# sensorbug_v1.net
KiCad netlist of a schematic drawn in EAGLE
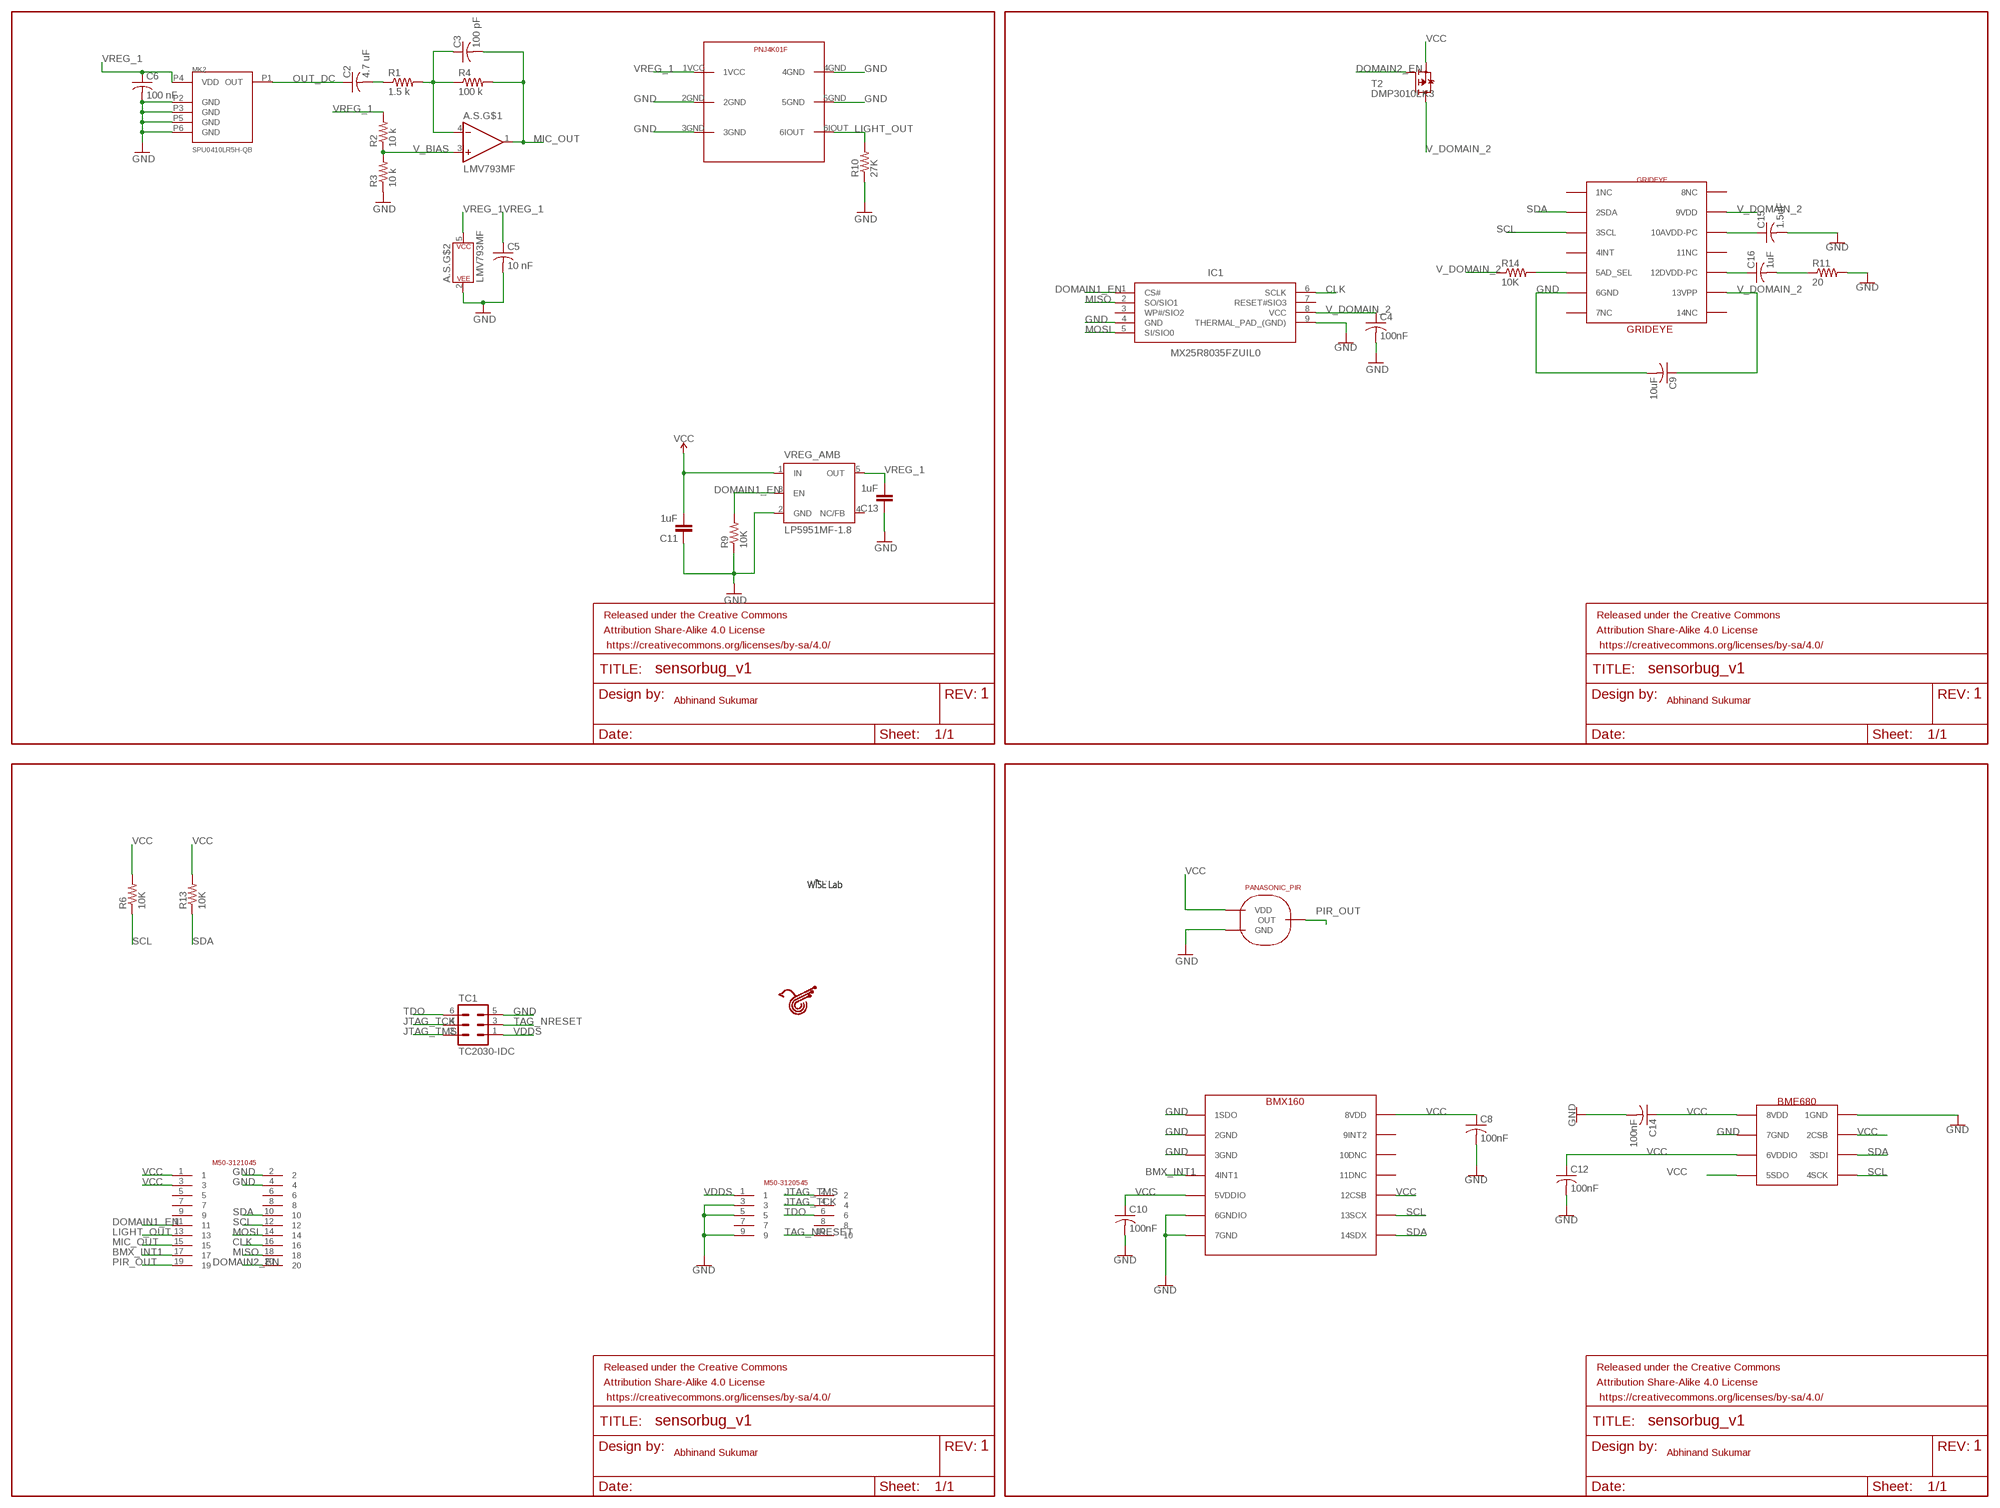
[diagram p0: schematic, sheet 1]

(export (version "E")
  (design (tool "Eeschema 10.0.6"))
  (components
    (comp (ref "A.S.")
      (value "LMV793MF")
      (footprint "eagle-import:SOT23-5")
      (libsource (lib "eagle-import") (part "LMV793MF"))
    )
    (comp (ref "BME")
      (value "BME680")
      (footprint "eagle-import:BME680_LGA")
      (libsource (lib "eagle-import") (part "BME680"))
    )
    (comp (ref "BMX")
      (value "BMX160")
      (footprint "eagle-import:LGA")
      (libsource (lib "eagle-import") (part "BMX160"))
    )
    (comp (ref "C2")
      (value "4.7 uF")
      (footprint "eagle-import:C0603")
      (libsource (lib "eagle-import") (part "C-USC0603"))
    )
    (comp (ref "C3")
      (value "100 pF")
      (footprint "eagle-import:C0603")
      (libsource (lib "eagle-import") (part "C-USC0603"))
    )
    (comp (ref "C4")
      (value "100nF")
      (footprint "eagle-import:C0603")
      (libsource (lib "eagle-import") (part "C-USC0603"))
    )
    (comp (ref "C5")
      (value "10 nF")
      (footprint "eagle-import:C0603")
      (libsource (lib "eagle-import") (part "C-USC0603"))
    )
    (comp (ref "C6")
      (value "100 nF")
      (footprint "eagle-import:C0603")
      (libsource (lib "eagle-import") (part "C-USC0603"))
    )
    (comp (ref "C8")
      (value "100nF")
      (footprint "eagle-import:C0603")
      (libsource (lib "eagle-import") (part "C-USC0603"))
    )
    (comp (ref "C9")
      (value "10uF")
      (footprint "eagle-import:C0603")
      (libsource (lib "eagle-import") (part "C-USC0603"))
    )
    (comp (ref "C10")
      (value "100nF")
      (footprint "eagle-import:C0603")
      (libsource (lib "eagle-import") (part "C-USC0603"))
    )
    (comp (ref "C11")
      (value "1uF")
      (footprint "eagle-import:C0603")
      (libsource (lib "eagle-import") (part "C-EUC0603"))
    )
    (comp (ref "C12")
      (value "100nF")
      (footprint "eagle-import:C0603")
      (libsource (lib "eagle-import") (part "C-USC0603"))
    )
    (comp (ref "C13")
      (value "1uF")
      (footprint "eagle-import:C0603")
      (libsource (lib "eagle-import") (part "C-EUC0603"))
    )
    (comp (ref "C14")
      (value "100nF")
      (footprint "eagle-import:C0603")
      (libsource (lib "eagle-import") (part "C-USC0603"))
    )
    (comp (ref "C15")
      (value "1.5uF")
      (footprint "eagle-import:C0603")
      (libsource (lib "eagle-import") (part "C-USC0603"))
    )
    (comp (ref "C16")
      (value "1uF")
      (footprint "eagle-import:C0603")
      (libsource (lib "eagle-import") (part "C-USC0603"))
    )
    (comp (ref "FRAME1")
      (value "FRAME-LETTER")
      (footprint "eagle-import:CREATIVE_COMMONS")
      (libsource (lib "eagle-import") (part "FRAME-LETTER"))
    )
    (comp (ref "FRAME2")
      (value "FRAME-LETTER")
      (footprint "eagle-import:CREATIVE_COMMONS")
      (libsource (lib "eagle-import") (part "FRAME-LETTER"))
    )
    (comp (ref "FRAME3")
      (value "FRAME-LETTER")
      (footprint "eagle-import:CREATIVE_COMMONS")
      (libsource (lib "eagle-import") (part "FRAME-LETTER"))
    )
    (comp (ref "FRAME4")
      (value "FRAME-LETTER")
      (footprint "eagle-import:CREATIVE_COMMONS")
      (libsource (lib "eagle-import") (part "FRAME-LETTER"))
    )
    (comp (ref "GRIDEYE")
      (value "GRIDEYE")
      (footprint "eagle-import:GRIDEYE")
      (libsource (lib "eagle-import") (part "GRIDEYE"))
    )
    (comp (ref "IC1")
      (value "MX25R8035FZUIL0")
      (footprint "eagle-import:USON-8L")
      (libsource (lib "eagle-import") (part "MX25R8035FZUIL0"))
    )
    (comp (ref "LIGHT")
      (value "PNJ4K01F")
      (footprint "eagle-import:PNJ4K01F")
      (libsource (lib "eagle-import") (part "PNJ4K01F"))
    )
    (comp (ref "MK2")
      (value "SPU0410LR5H-QB")
      (footprint "eagle-import:SPU0410LR5H-QB")
      (libsource (lib "eagle-import") (part "SPU0410LR5H-QB"))
    )
    (comp (ref "R1")
      (value "1.5 k")
      (footprint "eagle-import:R0603")
      (libsource (lib "eagle-import") (part "R-US_R0603"))
    )
    (comp (ref "R2")
      (value "10 k")
      (footprint "eagle-import:R0603")
      (libsource (lib "eagle-import") (part "R-US_R0603"))
    )
    (comp (ref "R3")
      (value "10 k")
      (footprint "eagle-import:R0603")
      (libsource (lib "eagle-import") (part "R-US_R0603"))
    )
    (comp (ref "R4")
      (value "100 k")
      (footprint "eagle-import:R0603")
      (libsource (lib "eagle-import") (part "R-US_R0603"))
    )
    (comp (ref "R6")
      (value "10K")
      (footprint "eagle-import:R0603")
      (libsource (lib "eagle-import") (part "R-US_R0603"))
    )
    (comp (ref "R9")
      (value "10K")
      (footprint "eagle-import:R0603")
      (libsource (lib "eagle-import") (part "R-US_R0603"))
    )
    (comp (ref "R10")
      (value "27K")
      (footprint "eagle-import:R0603")
      (libsource (lib "eagle-import") (part "R-US_R0603"))
    )
    (comp (ref "R11")
      (value "20")
      (footprint "eagle-import:R0603")
      (libsource (lib "eagle-import") (part "R-US_R0603"))
    )
    (comp (ref "R13")
      (value "10K")
      (footprint "eagle-import:R0603")
      (libsource (lib "eagle-import") (part "R-US_R0603"))
    )
    (comp (ref "R14")
      (value "10K")
      (footprint "eagle-import:R0603")
      (libsource (lib "eagle-import") (part "R-US_R0603"))
    )
    (comp (ref "T2")
      (value "DMP3010LK3")
      (footprint "eagle-import:TO252")
      (libsource (lib "eagle-import") (part "SPD30P06PTO252"))
    )
    (comp (ref "TC1")
      (value "TC2030-IDC")
      (footprint "eagle-import:TC2030-IDC")
      (libsource (lib "eagle-import") (part "TC2030-IDC"))
    )
    (comp (ref "U$2")
      (value "WISELAB_LOGO-M")
      (footprint "eagle-import:WISELAB_LOGO_M")
      (libsource (lib "eagle-import") (part "WISELAB_LOGO-M"))
    )
    (comp (ref "U$3")
      (value "EKMB1201112")
      (footprint "eagle-import:EKMB1201112")
      (libsource (lib "eagle-import") (part "EKMB1201112"))
    )
    (comp (ref "U$4")
      (value "M50-3121045")
      (footprint "eagle-import:M50-3121045")
      (libsource (lib "eagle-import") (part "M50-3121045"))
    )
    (comp (ref "U$5")
      (value "M50-3120545")
      (footprint "eagle-import:M50-3100545")
      (libsource (lib "eagle-import") (part "M50-3120545"))
    )
    (comp (ref "U$6")
      (value "OPENCHIR_LOGO_PCB-M")
      (footprint "eagle-import:OPENCHIRP_LOGO_M")
      (libsource (lib "eagle-import") (part "OPENCHIR_LOGO_PCB-M"))
    )
    (comp (ref "VREG_AMB")
      (value "LP5951MF-1.8")
      (footprint "eagle-import:SOT23-DBV")
      (libsource (lib "eagle-import") (part "LP5951MF-1.8"))
    )
  )
  (nets
    (net (code "1") (name "/BMX_INT1") (class "Default")
      (node (ref "BMX") (pin "4INT1") (pinfunction "4INT1_4INT1") (pintype "bidirectional"))
      (node (ref "U$4") (pin "17") (pinfunction "17_17") (pintype "bidirectional"))
    )
    (net (code "2") (name "/CLK") (class "Default")
      (node (ref "IC1") (pin "6") (pinfunction "SCLK_6") (pintype "input"))
      (node (ref "U$4") (pin "16") (pinfunction "16_16") (pintype "bidirectional"))
    )
    (net (code "3") (name "/DOMAIN1_EN") (class "Default")
      (node (ref "IC1") (pin "1") (pinfunction "CS#_1") (pintype "input"))
      (node (ref "R9") (pin "2") (pinfunction "2_2") (pintype "passive"))
      (node (ref "U$4") (pin "11") (pinfunction "11_11") (pintype "bidirectional"))
      (node (ref "VREG_AMB") (pin "3") (pinfunction "EN_3") (pintype "input"))
    )
    (net (code "4") (name "/DOMAIN2_EN") (class "Default")
      (node (ref "T2") (pin "1") (pinfunction "G_1") (pintype "passive"))
      (node (ref "U$4") (pin "20") (pinfunction "20_20") (pintype "bidirectional"))
    )
    (net (code "5") (name "/JTAG_TCK") (class "Default")
      (node (ref "TC1") (pin "4") (pinfunction "4_4") (pintype "passive"))
      (node (ref "U$5") (pin "4") (pinfunction "4_4") (pintype "bidirectional"))
    )
    (net (code "6") (name "/JTAG_TMS") (class "Default")
      (node (ref "TC1") (pin "2") (pinfunction "2_2") (pintype "passive"))
      (node (ref "U$5") (pin "2") (pinfunction "2_2") (pintype "bidirectional"))
    )
    (net (code "7") (name "/LIGHT_OUT") (class "Default")
      (node (ref "LIGHT") (pin "6IOUT") (pinfunction "6IOUT_6IOUT") (pintype "bidirectional"))
      (node (ref "R10") (pin "2") (pinfunction "2_2") (pintype "passive"))
      (node (ref "U$4") (pin "13") (pinfunction "13_13") (pintype "bidirectional"))
    )
    (net (code "8") (name "/MIC_OUT") (class "Default")
      (node (ref "A.S.") (pin "1") (pinfunction "OUT_1") (pintype "output"))
      (node (ref "C3") (pin "2") (pinfunction "2_2") (pintype "passive"))
      (node (ref "R4") (pin "2") (pinfunction "2_2") (pintype "passive"))
      (node (ref "U$4") (pin "15") (pinfunction "15_15") (pintype "bidirectional"))
    )
    (net (code "9") (name "/MISO") (class "Default")
      (node (ref "IC1") (pin "2") (pinfunction "SO/SIO1_2") (pintype "input"))
      (node (ref "U$4") (pin "18") (pinfunction "18_18") (pintype "bidirectional"))
    )
    (net (code "10") (name "/MOSI") (class "Default")
      (node (ref "IC1") (pin "5") (pinfunction "SI/SIO0_5") (pintype "input"))
      (node (ref "U$4") (pin "14") (pinfunction "14_14") (pintype "bidirectional"))
    )
    (net (code "11") (name "/OUT_DC") (class "Default")
      (node (ref "C2") (pin "1") (pinfunction "1_1") (pintype "passive"))
      (node (ref "MK2") (pin "P1") (pinfunction "OUT_P1") (pintype "output"))
    )
    (net (code "12") (name "/PIR_OUT") (class "Default")
      (node (ref "U$3") (pin "OUT") (pinfunction "OUT_OUT") (pintype "bidirectional"))
      (node (ref "U$4") (pin "19") (pinfunction "19_19") (pintype "bidirectional"))
    )
    (net (code "13") (name "/SCL") (class "Default")
      (node (ref "BME") (pin "4SCK") (pinfunction "4SCK_4SCK") (pintype "bidirectional"))
      (node (ref "BMX") (pin "13SCX") (pinfunction "13SCX_13SCX") (pintype "bidirectional"))
      (node (ref "GRIDEYE") (pin "3") (pinfunction "3SCL_3") (pintype "bidirectional"))
      (node (ref "R6") (pin "1") (pinfunction "1_1") (pintype "passive"))
      (node (ref "U$4") (pin "12") (pinfunction "12_12") (pintype "bidirectional"))
    )
    (net (code "14") (name "/SDA") (class "Default")
      (node (ref "BME") (pin "3SDI") (pinfunction "3SDI_3SDI") (pintype "bidirectional"))
      (node (ref "BMX") (pin "14SDX") (pinfunction "14SDX_14SDX") (pintype "bidirectional"))
      (node (ref "GRIDEYE") (pin "2") (pinfunction "2SDA_2") (pintype "bidirectional"))
      (node (ref "R13") (pin "1") (pinfunction "1_1") (pintype "passive"))
      (node (ref "U$4") (pin "10") (pinfunction "10_10") (pintype "bidirectional"))
    )
    (net (code "15") (name "/TAG_NRESET") (class "Default")
      (node (ref "TC1") (pin "3") (pinfunction "3_3") (pintype "passive"))
      (node (ref "U$5") (pin "10") (pinfunction "10_10") (pintype "bidirectional"))
    )
    (net (code "16") (name "/TDO") (class "Default")
      (node (ref "TC1") (pin "6") (pinfunction "6_6") (pintype "passive"))
      (node (ref "U$5") (pin "6") (pinfunction "6_6") (pintype "bidirectional"))
    )
    (net (code "17") (name "/VDDS") (class "Default")
      (node (ref "TC1") (pin "1") (pinfunction "1_1") (pintype "passive"))
      (node (ref "U$5") (pin "1") (pinfunction "1_1") (pintype "bidirectional"))
    )
    (net (code "18") (name "/VREG_1") (class "Default")
      (node (ref "A.S.") (pin "5") (pinfunction "P$V+_5") (pintype "bidirectional"))
      (node (ref "C13") (pin "2") (pinfunction "2_2") (pintype "passive"))
      (node (ref "C5") (pin "1") (pinfunction "1_1") (pintype "passive"))
      (node (ref "C6") (pin "1") (pinfunction "1_1") (pintype "passive"))
      (node (ref "LIGHT") (pin "1VCC") (pinfunction "1VCC_1VCC") (pintype "bidirectional"))
      (node (ref "MK2") (pin "P4") (pinfunction "VDD_P4") (pintype "power_in"))
      (node (ref "R2") (pin "2") (pinfunction "2_2") (pintype "passive"))
      (node (ref "VREG_AMB") (pin "5") (pinfunction "OUT_5") (pintype "output"))
    )
    (net (code "19") (name "/V_BIAS") (class "Default")
      (node (ref "A.S.") (pin "3") (pinfunction "+IN_3") (pintype "input"))
      (node (ref "R2") (pin "1") (pinfunction "1_1") (pintype "passive"))
      (node (ref "R3") (pin "2") (pinfunction "2_2") (pintype "passive"))
    )
    (net (code "20") (name "/V_DOMAIN_2") (class "Default")
      (node (ref "C4") (pin "1") (pinfunction "1_1") (pintype "passive"))
      (node (ref "C9") (pin "1") (pinfunction "1_1") (pintype "passive"))
      (node (ref "GRIDEYE") (pin "13") (pinfunction "13VPP_13") (pintype "bidirectional"))
      (node (ref "GRIDEYE") (pin "9") (pinfunction "9VDD_9") (pintype "bidirectional"))
      (node (ref "IC1") (pin "8") (pinfunction "VCC_8") (pintype "input"))
      (node (ref "R14") (pin "1") (pinfunction "1_1") (pintype "passive"))
      (node (ref "T2") (pin "3") (pinfunction "D_3") (pintype "passive"))
    )
    (net (code "21") (name "GND") (class "Default")
      (node (ref "A.S.") (pin "2") (pinfunction "P$V-_2") (pintype "bidirectional"))
      (node (ref "BME") (pin "1GND") (pinfunction "1GND_1GND") (pintype "bidirectional"))
      (node (ref "BME") (pin "7GND") (pinfunction "7GND_7GND") (pintype "bidirectional"))
      (node (ref "BMX") (pin "1SDO") (pinfunction "1SDO_1SDO") (pintype "bidirectional"))
      (node (ref "BMX") (pin "2GND") (pinfunction "2GND_2GND") (pintype "bidirectional"))
      (node (ref "BMX") (pin "3GND") (pinfunction "3GND_3GND") (pintype "bidirectional"))
      (node (ref "BMX") (pin "6GNDIO") (pinfunction "6GNDIO_6GNDIO") (pintype "bidirectional"))
      (node (ref "BMX") (pin "7GND") (pinfunction "7GND_7GND") (pintype "bidirectional"))
      (node (ref "C10") (pin "2") (pinfunction "2_2") (pintype "passive"))
      (node (ref "C11") (pin "1") (pinfunction "1_1") (pintype "passive"))
      (node (ref "C12") (pin "2") (pinfunction "2_2") (pintype "passive"))
      (node (ref "C13") (pin "1") (pinfunction "1_1") (pintype "passive"))
      (node (ref "C14") (pin "2") (pinfunction "2_2") (pintype "passive"))
      (node (ref "C15") (pin "2") (pinfunction "2_2") (pintype "passive"))
      (node (ref "C4") (pin "2") (pinfunction "2_2") (pintype "passive"))
      (node (ref "C5") (pin "2") (pinfunction "2_2") (pintype "passive"))
      (node (ref "C6") (pin "2") (pinfunction "2_2") (pintype "passive"))
      (node (ref "C8") (pin "2") (pinfunction "2_2") (pintype "passive"))
      (node (ref "C9") (pin "2") (pinfunction "2_2") (pintype "passive"))
      (node (ref "GRIDEYE") (pin "6") (pinfunction "6GND_6") (pintype "bidirectional"))
      (node (ref "IC1") (pin "4") (pinfunction "GND_4") (pintype "input"))
      (node (ref "IC1") (pin "9") (pinfunction "THERMAL_PAD_(GND)_9") (pintype "input"))
      (node (ref "LIGHT") (pin "2GND") (pinfunction "2GND_2GND") (pintype "bidirectional"))
      (node (ref "LIGHT") (pin "3GND") (pinfunction "3GND_3GND") (pintype "bidirectional"))
      (node (ref "LIGHT") (pin "4GND") (pinfunction "4GND_4GND") (pintype "bidirectional"))
      (node (ref "LIGHT") (pin "5GND") (pinfunction "5GND_5GND") (pintype "bidirectional"))
      (node (ref "MK2") (pin "P2") (pinfunction "GND_P2") (pintype "power_in"))
      (node (ref "MK2") (pin "P3") (pinfunction "GND_P3") (pintype "power_in"))
      (node (ref "MK2") (pin "P5") (pinfunction "GND_P5") (pintype "power_in"))
      (node (ref "MK2") (pin "P6") (pinfunction "GND_P6") (pintype "power_in"))
      (node (ref "R10") (pin "1") (pinfunction "1_1") (pintype "passive"))
      (node (ref "R11") (pin "2") (pinfunction "2_2") (pintype "passive"))
      (node (ref "R3") (pin "1") (pinfunction "1_1") (pintype "passive"))
      (node (ref "R9") (pin "1") (pinfunction "1_1") (pintype "passive"))
      (node (ref "TC1") (pin "5") (pinfunction "5_5") (pintype "passive"))
      (node (ref "U$3") (pin "GND") (pinfunction "GND_GND") (pintype "bidirectional"))
      (node (ref "U$4") (pin "2") (pinfunction "2_2") (pintype "bidirectional"))
      (node (ref "U$4") (pin "4") (pinfunction "4_4") (pintype "bidirectional"))
      (node (ref "U$5") (pin "3") (pinfunction "3_3") (pintype "bidirectional"))
      (node (ref "U$5") (pin "5") (pinfunction "5_5") (pintype "bidirectional"))
      (node (ref "U$5") (pin "9") (pinfunction "9_9") (pintype "bidirectional"))
      (node (ref "VREG_AMB") (pin "2") (pinfunction "GND_2") (pintype "power_in"))
    )
    (net (code "22") (name "Net-(A.S.A--IN)") (class "Default")
      (node (ref "A.S.") (pin "4") (pinfunction "-IN_4") (pintype "input"))
      (node (ref "C3") (pin "1") (pinfunction "1_1") (pintype "passive"))
      (node (ref "R1") (pin "2") (pinfunction "2_2") (pintype "passive"))
      (node (ref "R4") (pin "1") (pinfunction "1_1") (pintype "passive"))
    )
    (net (code "23") (name "Net-(C2-Pad2)") (class "Default")
      (node (ref "C2") (pin "2") (pinfunction "2_2") (pintype "passive"))
      (node (ref "R1") (pin "1") (pinfunction "1_1") (pintype "passive"))
    )
    (net (code "24") (name "Net-(C16-Pad2)") (class "Default")
      (node (ref "C16") (pin "2") (pinfunction "2_2") (pintype "passive"))
      (node (ref "R11") (pin "1") (pinfunction "1_1") (pintype "passive"))
    )
    (net (code "25") (name "Net-(GRIDEYE-5AD_SEL)") (class "Default")
      (node (ref "GRIDEYE") (pin "5") (pinfunction "5AD_SEL_5") (pintype "bidirectional"))
      (node (ref "R14") (pin "2") (pinfunction "2_2") (pintype "passive"))
    )
    (net (code "26") (name "Net-(GRIDEYE-10AVDD-PC)") (class "Default")
      (node (ref "C15") (pin "1") (pinfunction "1_1") (pintype "passive"))
      (node (ref "GRIDEYE") (pin "10") (pinfunction "10AVDD-PC_10") (pintype "bidirectional"))
    )
    (net (code "27") (name "Net-(GRIDEYE-12DVDD-PC)") (class "Default")
      (node (ref "C16") (pin "1") (pinfunction "1_1") (pintype "passive"))
      (node (ref "GRIDEYE") (pin "12") (pinfunction "12DVDD-PC_12") (pintype "bidirectional"))
    )
    (net (code "28") (name "VCC") (class "Default")
      (node (ref "BME") (pin "2CSB") (pinfunction "2CSB_2CSB") (pintype "bidirectional"))
      (node (ref "BME") (pin "5SDO") (pinfunction "5SDO_5SDO") (pintype "bidirectional"))
      (node (ref "BME") (pin "6VDDIO") (pinfunction "6VDDIO_6VDDIO") (pintype "bidirectional"))
      (node (ref "BME") (pin "8VDD") (pinfunction "8VDD_8VDD") (pintype "bidirectional"))
      (node (ref "BMX") (pin "12CSB") (pinfunction "12CSB_12CSB") (pintype "bidirectional"))
      (node (ref "BMX") (pin "5VDDIO") (pinfunction "5VDDIO_5VDDIO") (pintype "bidirectional"))
      (node (ref "BMX") (pin "8VDD") (pinfunction "8VDD_8VDD") (pintype "bidirectional"))
      (node (ref "C10") (pin "1") (pinfunction "1_1") (pintype "passive"))
      (node (ref "C11") (pin "2") (pinfunction "2_2") (pintype "passive"))
      (node (ref "C12") (pin "1") (pinfunction "1_1") (pintype "passive"))
      (node (ref "C14") (pin "1") (pinfunction "1_1") (pintype "passive"))
      (node (ref "C8") (pin "1") (pinfunction "1_1") (pintype "passive"))
      (node (ref "R13") (pin "2") (pinfunction "2_2") (pintype "passive"))
      (node (ref "R6") (pin "2") (pinfunction "2_2") (pintype "passive"))
      (node (ref "T2") (pin "2") (pinfunction "S_2") (pintype "passive"))
      (node (ref "U$3") (pin "VDD") (pinfunction "VDD_VDD") (pintype "bidirectional"))
      (node (ref "U$4") (pin "1") (pinfunction "1_1") (pintype "bidirectional"))
      (node (ref "U$4") (pin "3") (pinfunction "3_3") (pintype "bidirectional"))
      (node (ref "VREG_AMB") (pin "1") (pinfunction "IN_1") (pintype "input"))
    )
    (net (code "29") (name "unconnected-(BMX-Pad9INT2)") (class "Default")
      (node (ref "BMX") (pin "9INT2") (pinfunction "9INT2_9INT2") (pintype "bidirectional"))
    )
    (net (code "30") (name "unconnected-(BMX-Pad10DNC)") (class "Default")
      (node (ref "BMX") (pin "10DNC") (pinfunction "10DNC_10DNC") (pintype "bidirectional"))
    )
    (net (code "31") (name "unconnected-(BMX-Pad11DNC)") (class "Default")
      (node (ref "BMX") (pin "11DNC") (pinfunction "11DNC_11DNC") (pintype "bidirectional"))
    )
    (net (code "32") (name "unconnected-(GRIDEYE-1NC-Pad1)") (class "Default")
      (node (ref "GRIDEYE") (pin "1") (pinfunction "1NC_1") (pintype "bidirectional"))
    )
    (net (code "33") (name "unconnected-(GRIDEYE-4INT-Pad4)") (class "Default")
      (node (ref "GRIDEYE") (pin "4") (pinfunction "4INT_4") (pintype "bidirectional"))
    )
    (net (code "34") (name "unconnected-(GRIDEYE-7NC-Pad7)") (class "Default")
      (node (ref "GRIDEYE") (pin "7") (pinfunction "7NC_7") (pintype "bidirectional"))
    )
    (net (code "35") (name "unconnected-(GRIDEYE-8NC-Pad8)") (class "Default")
      (node (ref "GRIDEYE") (pin "8") (pinfunction "8NC_8") (pintype "bidirectional"))
    )
    (net (code "36") (name "unconnected-(GRIDEYE-11NC-Pad11)") (class "Default")
      (node (ref "GRIDEYE") (pin "11") (pinfunction "11NC_11") (pintype "bidirectional"))
    )
    (net (code "37") (name "unconnected-(GRIDEYE-14NC-Pad14)") (class "Default")
      (node (ref "GRIDEYE") (pin "14") (pinfunction "14NC_14") (pintype "bidirectional"))
    )
    (net (code "38") (name "unconnected-(IC1-RESET#SIO3-Pad7)") (class "Default")
      (node (ref "IC1") (pin "7") (pinfunction "RESET#SIO3_7") (pintype "input"))
    )
    (net (code "39") (name "unconnected-(IC1-WP#{slash}SIO2-Pad3)") (class "Default")
      (node (ref "IC1") (pin "3") (pinfunction "WP#/SIO2_3") (pintype "input"))
    )
    (net (code "40") (name "unconnected-(U$4-Pad5)") (class "Default")
      (node (ref "U$4") (pin "5") (pinfunction "5_5") (pintype "bidirectional"))
    )
    (net (code "41") (name "unconnected-(U$4-Pad6)") (class "Default")
      (node (ref "U$4") (pin "6") (pinfunction "6_6") (pintype "bidirectional"))
    )
    (net (code "42") (name "unconnected-(U$4-Pad7)") (class "Default")
      (node (ref "U$4") (pin "7") (pinfunction "7_7") (pintype "bidirectional"))
    )
    (net (code "43") (name "unconnected-(U$4-Pad8)") (class "Default")
      (node (ref "U$4") (pin "8") (pinfunction "8_8") (pintype "bidirectional"))
    )
    (net (code "44") (name "unconnected-(U$4-Pad9)") (class "Default")
      (node (ref "U$4") (pin "9") (pinfunction "9_9") (pintype "bidirectional"))
    )
    (net (code "45") (name "unconnected-(U$5-Pad7)") (class "Default")
      (node (ref "U$5") (pin "7") (pinfunction "7_7") (pintype "bidirectional"))
    )
    (net (code "46") (name "unconnected-(U$5-Pad8)") (class "Default")
      (node (ref "U$5") (pin "8") (pinfunction "8_8") (pintype "bidirectional"))
    )
    (net (code "47") (name "unconnected-(VREG_AMB-NC{slash}FB-Pad4)") (class "Default")
      (node (ref "VREG_AMB") (pin "4") (pinfunction "NC/FB_4") (pintype "passive"))
    )
  )
)
